# IDCI_WifiNode_PWR.net
KiCad netlist of a schematic drawn in Altium Designer
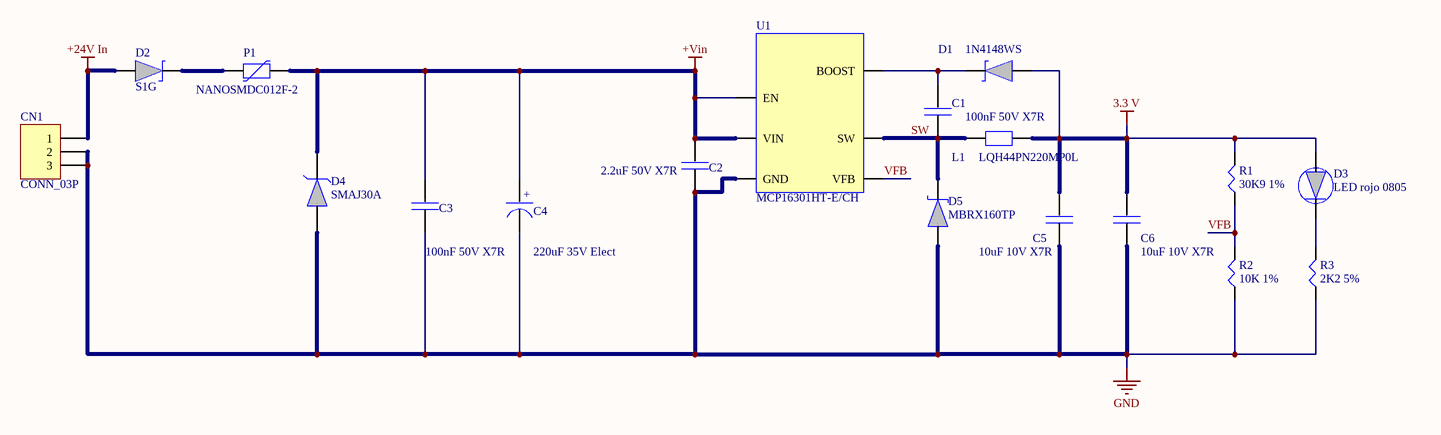
[diagram p0: IDCI_WifiNode_PWR.SchDoc]

(export (version "E")
  (design (tool "Eeschema 10.0.6"))
  (components
    (comp (ref "C1")
      (value "100nF 50V X7R")
      (description "100nF x 50v")
      (libsource (lib "IDCI_WifiNode_2_R00") (part "Capacitor"))
    )
    (comp (ref "C2")
      (value "2.2uF 50V X7R")
      (description "100nF x 50v")
      (libsource (lib "IDCI_WifiNode_2_R00") (part "Capacitor"))
    )
    (comp (ref "C3")
      (value "100nF 50V X7R")
      (description "100nF x 50v")
      (libsource (lib "IDCI_WifiNode_2_R00") (part "Capacitor"))
    )
    (comp (ref "C4")
      (value "220uF 35V Elect")
      (description "Capacitor polarizado")
      (libsource (lib "IDCI_WifiNode_2_R00") (part "POL_CAP"))
    )
    (comp (ref "C5")
      (value "10uF 10V X7R")
      (description "100nF x 50v")
      (libsource (lib "IDCI_WifiNode_2_R00") (part "Capacitor"))
    )
    (comp (ref "C6")
      (value "10uF 10V X7R")
      (description "100nF x 50v")
      (libsource (lib "IDCI_WifiNode_2_R00") (part "Capacitor"))
    )
    (comp (ref "CN1")
      (value "CONN_03P")
      (description "Connector Generic 3 Vias")
      (libsource (lib "IDCI_WifiNode_2_R00") (part "CONN_03P"))
    )
    (comp (ref "D1") (value "1N4148WS") (libsource (lib "Schlib1") (part "TVS_DIODE")))
    (comp (ref "D2") (value "S1G") (libsource (lib "Schlib1") (part "TVS_DIODE")))
    (comp (ref "D3") (value "LED rojo 0805") (libsource (lib "Schlib1") (part "LED_DIODE")))
    (comp (ref "D4") (value "SMAJ30A") (libsource (lib "IDCI_WifiNode_2_R00") (part "ZENER_DIODE")))
    (comp (ref "D5") (value "MBRX160TP") (libsource (lib "Schlib1") (part "TVS_DIODE")))
    (comp (ref "L1")
      (value "LQH44PN220MP0L")
      (description "Inductor")
      (libsource (lib "Schlib1") (part "Inductor"))
    )
    (comp (ref "P1")
      (value "NANOSMDC012F-2")
      (description "Polyswitch")
      (libsource (lib "Schlib1") (part "Polyswitch"))
    )
    (comp (ref "R1") (value "30K9 1%") (libsource (lib "IDCI_WifiNode_2_R00") (part "Resistor")))
    (comp (ref "R2") (value "10K 1%") (libsource (lib "IDCI_WifiNode_2_R00") (part "Resistor")))
    (comp (ref "R3") (value "2K2 5%") (libsource (lib "IDCI_WifiNode_2_R00") (part "Resistor")))
    (comp (ref "U1")
      (value "MCP16301HT-E/CH")
      (description "Driver Switching")
      (libsource (lib "Schlib1") (part "Integrado"))
    )
  )
  (nets
    (net (code "1") (name "+24V In") (class "Default")
      (node (ref "CN1") (pin "1") (pinfunction "1_1") (pintype "passive"))
      (node (ref "D2") (pin "34") (pinfunction "34_34") (pintype "passive"))
    )
    (net (code "2") (name "+Vin") (class "Default")
      (node (ref "C2") (pin "39") (pinfunction "39_39") (pintype "passive"))
      (node (ref "C3") (pin "39") (pinfunction "39_39") (pintype "passive"))
      (node (ref "C4") (pin "36") (pinfunction "36_36") (pintype "passive"))
      (node (ref "D4") (pin "33") (pinfunction "33_33") (pintype "passive"))
      (node (ref "P1") (pin "40") (pinfunction "40_40") (pintype "passive"))
      (node (ref "U1") (pin "49") (pinfunction "EN_49") (pintype "passive"))
      (node (ref "U1") (pin "50") (pinfunction "VIN_50") (pintype "passive"))
    )
    (net (code "3") (name "/SW") (class "Default")
      (node (ref "C1") (pin "38") (pinfunction "38_38") (pintype "passive"))
      (node (ref "D5") (pin "35") (pinfunction "35_35") (pintype "passive"))
      (node (ref "L1") (pin "45") (pinfunction "45_45") (pintype "passive"))
      (node (ref "U1") (pin "52") (pinfunction "SW_52") (pintype "passive"))
    )
    (net (code "4") (name "/VFB") (class "Default")
      (node (ref "R1") (pin "47") (pinfunction "47_47") (pintype "passive"))
      (node (ref "R2") (pin "48") (pinfunction "48_48") (pintype "passive"))
      (node (ref "U1") (pin "54") (pinfunction "VFB_54") (pintype "passive"))
    )
    (net (code "5") (name "3.3 V") (class "Default")
      (node (ref "C5") (pin "39") (pinfunction "39_39") (pintype "passive"))
      (node (ref "C6") (pin "39") (pinfunction "39_39") (pintype "passive"))
      (node (ref "D1") (pin "34") (pinfunction "34_34") (pintype "passive"))
      (node (ref "D3") (pin "31") (pinfunction "31_31") (pintype "passive"))
      (node (ref "L1") (pin "46") (pinfunction "46_46") (pintype "passive"))
      (node (ref "R1") (pin "48") (pinfunction "48_48") (pintype "passive"))
    )
    (net (code "6") (name "GND") (class "Default")
      (node (ref "C2") (pin "38") (pinfunction "38_38") (pintype "passive"))
      (node (ref "C3") (pin "38") (pinfunction "38_38") (pintype "passive"))
      (node (ref "C4") (pin "37") (pinfunction "37_37") (pintype "passive"))
      (node (ref "C5") (pin "38") (pinfunction "38_38") (pintype "passive"))
      (node (ref "C6") (pin "38") (pinfunction "38_38") (pintype "passive"))
      (node (ref "CN1") (pin "2") (pinfunction "2_2") (pintype "passive"))
      (node (ref "CN1") (pin "3") (pinfunction "3_3") (pintype "passive"))
      (node (ref "D4") (pin "32") (pinfunction "32_32") (pintype "passive"))
      (node (ref "D5") (pin "34") (pinfunction "34_34") (pintype "passive"))
      (node (ref "R2") (pin "47") (pinfunction "47_47") (pintype "passive"))
      (node (ref "R3") (pin "47") (pinfunction "47_47") (pintype "passive"))
      (node (ref "U1") (pin "51") (pinfunction "GND_51") (pintype "passive"))
    )
    (net (code "7") (name "Net-(D2-Pad35)") (class "Default")
      (node (ref "D2") (pin "35") (pinfunction "35_35") (pintype "passive"))
      (node (ref "P1") (pin "41") (pinfunction "41_41") (pintype "passive"))
    )
    (net (code "8") (name "Net-(D3-Pad30)") (class "Default")
      (node (ref "D3") (pin "30") (pinfunction "30_30") (pintype "passive"))
      (node (ref "R3") (pin "48") (pinfunction "48_48") (pintype "passive"))
    )
    (net (code "9") (name "Net-(U1-BOOST)") (class "Default")
      (node (ref "C1") (pin "39") (pinfunction "39_39") (pintype "passive"))
      (node (ref "D1") (pin "35") (pinfunction "35_35") (pintype "passive"))
      (node (ref "U1") (pin "53") (pinfunction "BOOST_53") (pintype "passive"))
    )
  )
)
